# TEMPLATE_Circuit.net
KiCad netlist of a schematic drawn in Altium Designer
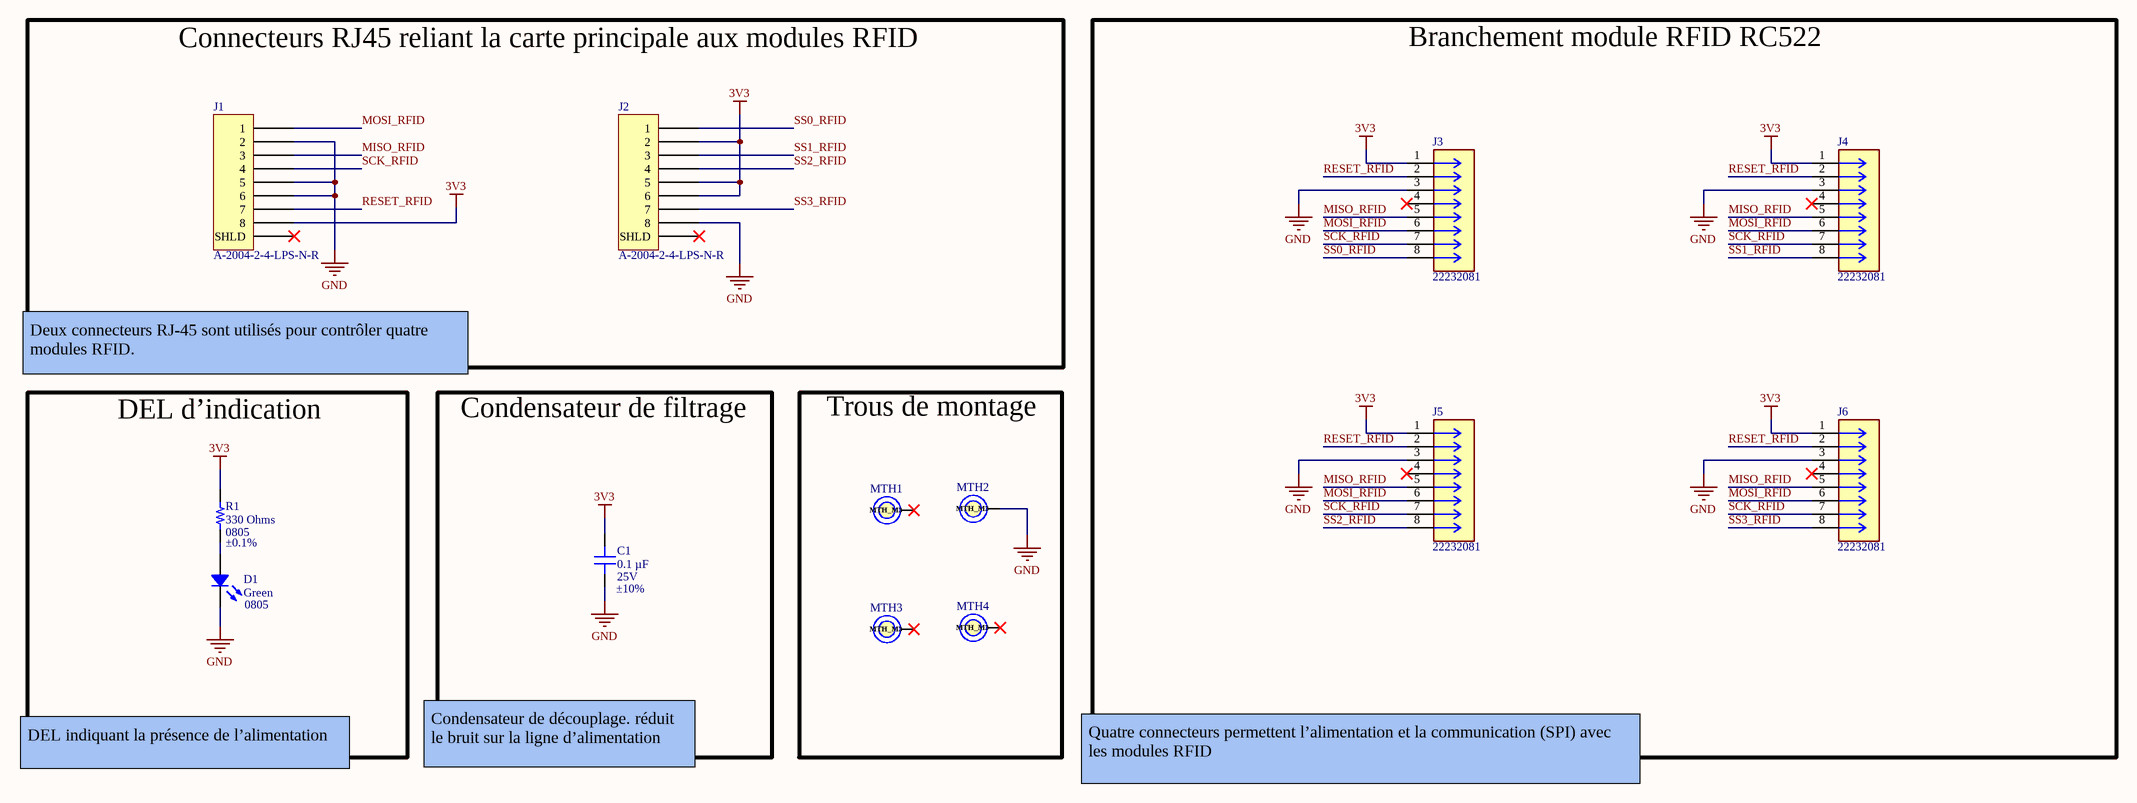
[diagram p0: TEMPLATE_Circuit.SchDoc]

(export (version "E")
  (design (tool "Eeschema 10.0.6"))
  (components
    (comp (ref "C1")
      (value "0.1 µF")
      (footprint "CAP 0805_2012")
      (description "CAP CER 0.1UF 25V X7R 0805")
      (fields
        (field (name "PART NUMBER") "0805J0250104KXT")
        (field (name "CAPACITANCE") "0.1 µF")
        (field (name "MANUFACTURER") "Knowles Syfer")
        (field (name "TOLERANCE") "±10%")
        (field (name "VOLTAGE - RATED") "25V")
      )
      (libsource (lib "Celestial Altium Library - altium_library") (part "Capacitor"))
    )
    (comp (ref "D1")
      (value "Green")
      (footprint "LED 0805_2012 GREEN")
      (description "LED GREEN 0805 SMD")
      (fields
        (field (name "PART NUMBER") "5975316507F")
        (field (name "MANUFACTURER") "Dialight")
        (field (name "SUPPLIER DEVICE PACKAGE") "0805")
      )
      (libsource (lib "Celestial Altium Library - altium_library") (part "LED"))
    )
    (comp (ref "J1")
      (value "A-2004-2-4-LPS-N-R")
      (footprint "ASSMANN A-2004-2-4-LPS-N-R")
      (description "CONN MOD JACK 8P8C R/A SHIELDED")
      (fields (field (name "MANUFACTURER") "Assmann WSW Components"))
      (libsource (lib "Celestial Altium Library - altium_library") (part "Modular Jack with Shield"))
    )
    (comp (ref "J2")
      (value "A-2004-2-4-LPS-N-R")
      (footprint "ASSMANN A-2004-2-4-LPS-N-R")
      (description "CONN MOD JACK 8P8C R/A SHIELDED")
      (fields (field (name "MANUFACTURER") "Assmann WSW Components"))
      (libsource (lib "Celestial Altium Library - altium_library") (part "Modular Jack with Shield"))
    )
    (comp (ref "J3")
      (value "22232081")
      (footprint "CONN_A-6373-08A_MOL")
      (libsource (lib "22232081") (part "22232081"))
    )
    (comp (ref "J4")
      (value "22232081")
      (footprint "CONN_A-6373-08A_MOL")
      (libsource (lib "22232081") (part "22232081"))
    )
    (comp (ref "J5")
      (value "22232081")
      (footprint "CONN_A-6373-08A_MOL")
      (libsource (lib "22232081") (part "22232081"))
    )
    (comp (ref "J6")
      (value "22232081")
      (footprint "CONN_A-6373-08A_MOL")
      (libsource (lib "22232081") (part "22232081"))
    )
    (comp (ref "MTH1")
      (value "MTH_M3")
      (footprint "MTH_M3")
      (description "MTH - MOUNTING HOLE M3 PLATED - M3")
      (fields (field (name "SOURCE") "CEGEP_SHERBROOKE_TGE_LIBRARY.SchLib"))
      (libsource (lib "Cegep de Sherbrooke") (part "MTH_M7"))
    )
    (comp (ref "MTH2")
      (value "MTH_M3")
      (footprint "MTH_M3")
      (description "MTH - MOUNTING HOLE M3 PLATED - M3")
      (fields (field (name "SOURCE") "CEGEP_SHERBROOKE_TGE_LIBRARY.SchLib"))
      (libsource (lib "Cegep de Sherbrooke") (part "MTH_M7"))
    )
    (comp (ref "MTH3")
      (value "MTH_M3")
      (footprint "MTH_M3")
      (description "MTH - MOUNTING HOLE M3 PLATED - M3")
      (fields (field (name "SOURCE") "CEGEP_SHERBROOKE_TGE_LIBRARY.SchLib"))
      (libsource (lib "Cegep de Sherbrooke") (part "MTH_M7"))
    )
    (comp (ref "MTH4")
      (value "MTH_M3")
      (footprint "MTH_M3")
      (description "MTH - MOUNTING HOLE M3 PLATED - M3")
      (fields (field (name "SOURCE") "CEGEP_SHERBROOKE_TGE_LIBRARY.SchLib"))
      (libsource (lib "Cegep de Sherbrooke") (part "MTH_M7"))
    )
    (comp (ref "R1")
      (value "330 Ohms")
      (footprint "RES 0805_2012")
      (description "RES SMD 330 OHM 0.1% 1/4W 0805")
      (fields
        (field (name "PART NUMBER") "ERJ-PB6B3300V")
        (field (name "MANUFACTURER") "Panasonic Electronic Components")
        (field (name "SUPPLIER DEVICE PACKAGE") "0805")
        (field (name "TOLERANCE") "±0.1%")
      )
      (libsource (lib "Celestial Altium Library - altium_library") (part "Resistor"))
    )
  )
  (nets
    (net (code "1") (name "/MISO_RFID") (class "Default")
      (node (ref "J1") (pin "3") (pinfunction "3_3") (pintype "passive"))
      (node (ref "J3") (pin "5") (pinfunction "5_5") (pintype "passive"))
      (node (ref "J4") (pin "5") (pinfunction "5_5") (pintype "passive"))
      (node (ref "J5") (pin "5") (pinfunction "5_5") (pintype "passive"))
      (node (ref "J6") (pin "5") (pinfunction "5_5") (pintype "passive"))
    )
    (net (code "2") (name "/MOSI_RFID") (class "Default")
      (node (ref "J1") (pin "1") (pinfunction "1_1") (pintype "passive"))
      (node (ref "J3") (pin "6") (pinfunction "6_6") (pintype "passive"))
      (node (ref "J4") (pin "6") (pinfunction "6_6") (pintype "passive"))
      (node (ref "J5") (pin "6") (pinfunction "6_6") (pintype "passive"))
      (node (ref "J6") (pin "6") (pinfunction "6_6") (pintype "passive"))
    )
    (net (code "3") (name "/RESET_RFID") (class "Default")
      (node (ref "J1") (pin "7") (pinfunction "7_7") (pintype "passive"))
      (node (ref "J3") (pin "2") (pinfunction "2_2") (pintype "passive"))
      (node (ref "J4") (pin "2") (pinfunction "2_2") (pintype "passive"))
      (node (ref "J5") (pin "2") (pinfunction "2_2") (pintype "passive"))
      (node (ref "J6") (pin "2") (pinfunction "2_2") (pintype "passive"))
    )
    (net (code "4") (name "/SCK_RFID") (class "Default")
      (node (ref "J1") (pin "4") (pinfunction "4_4") (pintype "passive"))
      (node (ref "J3") (pin "7") (pinfunction "7_7") (pintype "passive"))
      (node (ref "J4") (pin "7") (pinfunction "7_7") (pintype "passive"))
      (node (ref "J5") (pin "7") (pinfunction "7_7") (pintype "passive"))
      (node (ref "J6") (pin "7") (pinfunction "7_7") (pintype "passive"))
    )
    (net (code "5") (name "/SS0_RFID") (class "Default")
      (node (ref "J2") (pin "1") (pinfunction "1_1") (pintype "passive"))
      (node (ref "J3") (pin "8") (pinfunction "8_8") (pintype "passive"))
    )
    (net (code "6") (name "/SS1_RFID") (class "Default")
      (node (ref "J2") (pin "3") (pinfunction "3_3") (pintype "passive"))
      (node (ref "J4") (pin "8") (pinfunction "8_8") (pintype "passive"))
    )
    (net (code "7") (name "/SS2_RFID") (class "Default")
      (node (ref "J2") (pin "4") (pinfunction "4_4") (pintype "passive"))
      (node (ref "J5") (pin "8") (pinfunction "8_8") (pintype "passive"))
    )
    (net (code "8") (name "/SS3_RFID") (class "Default")
      (node (ref "J2") (pin "7") (pinfunction "7_7") (pintype "passive"))
      (node (ref "J6") (pin "8") (pinfunction "8_8") (pintype "passive"))
    )
    (net (code "9") (name "3V3") (class "Default")
      (node (ref "C1") (pin "2") (pinfunction "2_2") (pintype "passive"))
      (node (ref "J1") (pin "8") (pinfunction "8_8") (pintype "passive"))
      (node (ref "J2") (pin "2") (pinfunction "2_2") (pintype "passive"))
      (node (ref "J2") (pin "5") (pinfunction "5_5") (pintype "passive"))
      (node (ref "J2") (pin "6") (pinfunction "6_6") (pintype "passive"))
      (node (ref "J3") (pin "1") (pinfunction "1_1") (pintype "passive"))
      (node (ref "J4") (pin "1") (pinfunction "1_1") (pintype "passive"))
      (node (ref "J5") (pin "1") (pinfunction "1_1") (pintype "passive"))
      (node (ref "J6") (pin "1") (pinfunction "1_1") (pintype "passive"))
      (node (ref "R1") (pin "2") (pinfunction "2_2") (pintype "passive"))
    )
    (net (code "10") (name "GND") (class "Default")
      (node (ref "C1") (pin "1") (pinfunction "1_1") (pintype "passive"))
      (node (ref "D1") (pin "2") (pinfunction "2_2") (pintype "passive"))
      (node (ref "J1") (pin "2") (pinfunction "2_2") (pintype "passive"))
      (node (ref "J1") (pin "5") (pinfunction "5_5") (pintype "passive"))
      (node (ref "J1") (pin "6") (pinfunction "6_6") (pintype "passive"))
      (node (ref "J2") (pin "8") (pinfunction "8_8") (pintype "passive"))
      (node (ref "J3") (pin "3") (pinfunction "3_3") (pintype "passive"))
      (node (ref "J4") (pin "3") (pinfunction "3_3") (pintype "passive"))
      (node (ref "J5") (pin "3") (pinfunction "3_3") (pintype "passive"))
      (node (ref "J6") (pin "3") (pinfunction "3_3") (pintype "passive"))
      (node (ref "MTH2") (pin "1") (pinfunction "1_1") (pintype "passive"))
    )
    (net (code "11") (name "Net-(D1-Pad1)") (class "Default")
      (node (ref "D1") (pin "1") (pinfunction "1_1") (pintype "passive"))
      (node (ref "R1") (pin "1") (pinfunction "1_1") (pintype "passive"))
    )
    (net (code "12") (name "unconnected-(J1-SHLD-PadS)") (class "Default")
      (node (ref "J1") (pin "S") (pinfunction "SHLD_S") (pintype "passive+no_connect"))
    )
    (net (code "13") (name "unconnected-(J2-SHLD-PadS)") (class "Default")
      (node (ref "J2") (pin "S") (pinfunction "SHLD_S") (pintype "passive+no_connect"))
    )
    (net (code "14") (name "unconnected-(J3-Pad4)") (class "Default")
      (node (ref "J3") (pin "4") (pinfunction "4_4") (pintype "passive+no_connect"))
    )
    (net (code "15") (name "unconnected-(J4-Pad4)") (class "Default")
      (node (ref "J4") (pin "4") (pinfunction "4_4") (pintype "passive+no_connect"))
    )
    (net (code "16") (name "unconnected-(J5-Pad4)") (class "Default")
      (node (ref "J5") (pin "4") (pinfunction "4_4") (pintype "passive+no_connect"))
    )
    (net (code "17") (name "unconnected-(J6-Pad4)") (class "Default")
      (node (ref "J6") (pin "4") (pinfunction "4_4") (pintype "passive+no_connect"))
    )
    (net (code "18") (name "unconnected-(MTH1-Pad1)") (class "Default")
      (node (ref "MTH1") (pin "1") (pinfunction "1_1") (pintype "passive+no_connect"))
    )
    (net (code "19") (name "unconnected-(MTH3-Pad1)") (class "Default")
      (node (ref "MTH3") (pin "1") (pinfunction "1_1") (pintype "passive+no_connect"))
    )
    (net (code "20") (name "unconnected-(MTH4-Pad1)") (class "Default")
      (node (ref "MTH4") (pin "1") (pinfunction "1_1") (pintype "passive+no_connect"))
    )
  )
)
